# 15_FLASH-NAND_FLASH.net
KiCad netlist of a schematic drawn in Altium Designer
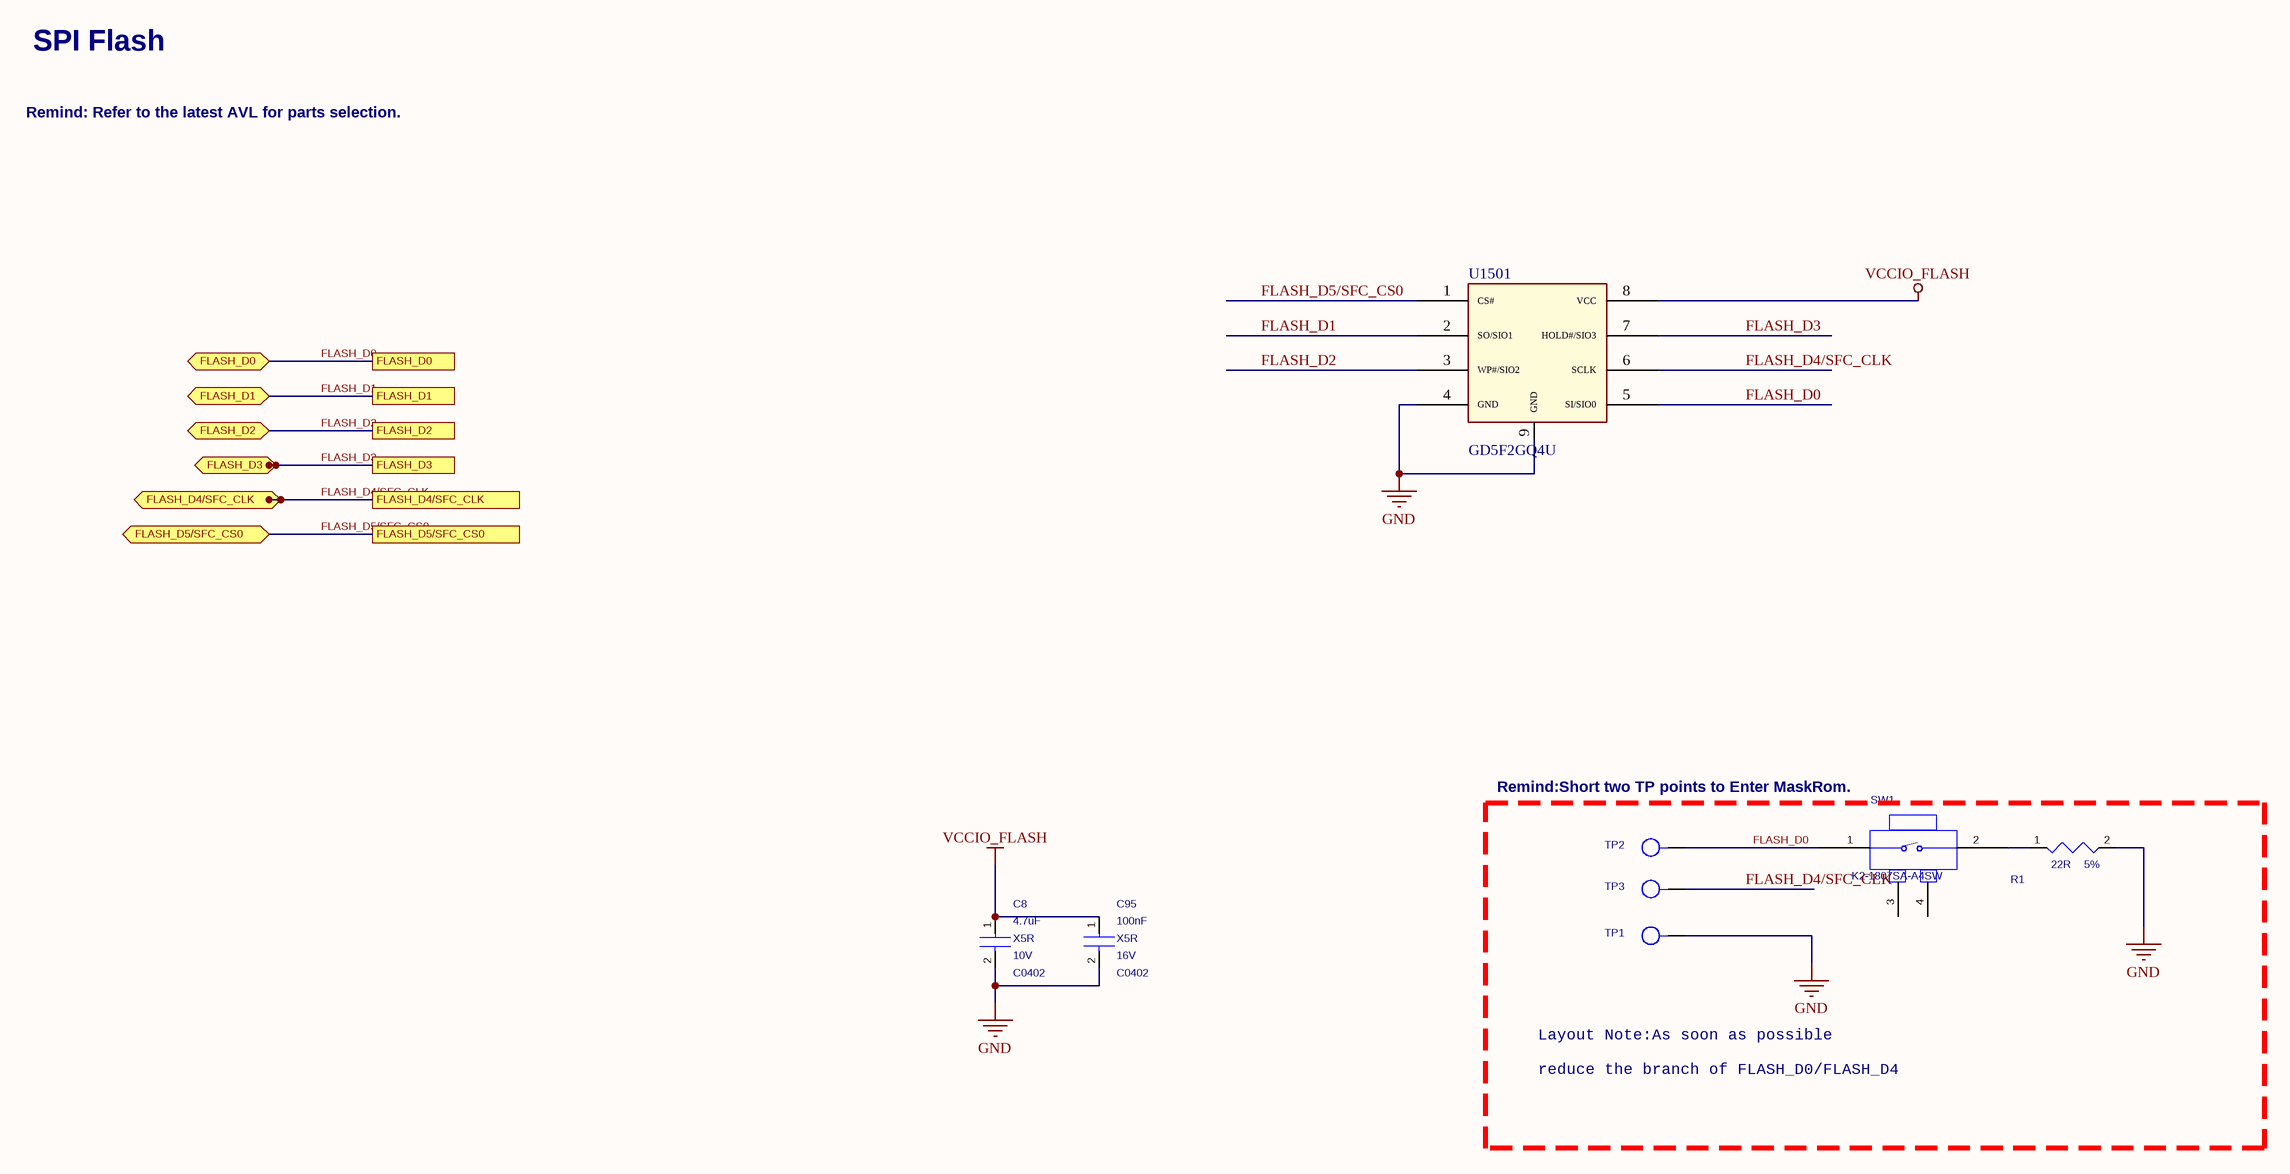
[diagram p0: 15_FLASH-NAND_FLASH.SchDoc]

(export (version "E")
  (design (tool "Eeschema 10.0.6"))
  (components
    (comp (ref "C8")
      (value "4.7uF")
      (footprint "C0402")
      (description "cap,4.70uF,+/-10%,10V,X5R,C0402")
      (fields
        (field (name "DIELECTRIC") "X5R")
        (field (name "VOLTAGE") "10V")
        (field (name "TOLERANCE") "10%")
        (field (name "MANUFACTURER") "TDK")
        (field (name "PCB DECAL") "C0402")
        (field (name "CREATED_BY") "JJJ")
      )
      (libsource (lib "*") (part "CAP_NP_2"))
    )
    (comp (ref "C95")
      (value "100nF")
      (footprint "C0402")
      (description "cap,100.00nF,+/-10%,16V,X5R,C0402")
      (fields
        (field (name "MANUFACTURER") "TDK")
        (field (name "TOLERANCE") "10%")
        (field (name "VOLTAGE") "16V")
        (field (name "DIELECTRIC") "X5R")
        (field (name "PCB DECAL") "C0402")
        (field (name "CREATED_BY") "JJJ")
      )
      (libsource (lib "*") (part "CAP_NP_2"))
    )
    (comp (ref "R1")
      (value "22R")
      (footprint "R0402")
      (description "?用厚膜电阻,22R,+/-5%,R0402,1/16W.")
      (fields
        (field (name "TOLERANCE") "5%")
        (field (name "MANUFACTURER") "YAGEO")
        (field (name "Comment") "RESISTOR")
        (field (name "CREATED_BY") "YTL")
      )
      (libsource (lib "*") (part "RESISTOR"))
    )
    (comp (ref "SW1")
      (value "K2-1807SA-A4SW")
      (footprint "P2")
      (fields (field (name "MANUFACTURER") "HRO"))
      (libsource (lib "*") (part "K2-1807SA-A4SW"))
    )
    (comp (ref "TP1") (value "TP") (footprint "TEST") (libsource (lib "*") (part "TP")))
    (comp (ref "TP2") (value "TP") (footprint "TEST") (libsource (lib "*") (part "TP")))
    (comp (ref "TP3") (value "TP") (footprint "TEST") (libsource (lib "*") (part "TP")))
    (comp (ref "U1501") (value "GD5F2GQ4U") (footprint "LGA8") (libsource (lib "amenuo") (part "GD5F2Q4U")))
  )
  (nets
    (net (code "1") (name "/FLASH_D0") (class "Default")
      (node (ref "SW1") (pin "1") (pinfunction "1_1") (pintype "passive"))
      (node (ref "TP2") (pin "1") (pinfunction "1_1") (pintype "passive"))
      (node (ref "U1501") (pin "5") (pinfunction "SI/SIO0_5") (pintype "passive"))
    )
    (net (code "2") (name "/FLASH_D1") (class "Default")
      (node (ref "U1501") (pin "2") (pinfunction "SO/SIO1_2") (pintype "passive"))
    )
    (net (code "3") (name "/FLASH_D2") (class "Default")
      (node (ref "U1501") (pin "3") (pinfunction "WP#/SIO2_3") (pintype "passive"))
    )
    (net (code "4") (name "/FLASH_D3") (class "Default")
      (node (ref "U1501") (pin "7") (pinfunction "HOLD#/SIO3_7") (pintype "passive"))
    )
    (net (code "5") (name "/FLASH_D4{slash}SFC_CLK") (class "Default")
      (node (ref "TP3") (pin "1") (pinfunction "1_1") (pintype "passive"))
      (node (ref "U1501") (pin "6") (pinfunction "SCLK_6") (pintype "passive"))
    )
    (net (code "6") (name "/FLASH_D5{slash}SFC_CS0") (class "Default")
      (node (ref "U1501") (pin "1") (pinfunction "CS#_1") (pintype "passive"))
    )
    (net (code "7") (name "GND") (class "Default")
      (node (ref "C8") (pin "2") (pinfunction "2_2") (pintype "passive"))
      (node (ref "C95") (pin "2") (pinfunction "2_2") (pintype "passive"))
      (node (ref "R1") (pin "2") (pinfunction "2_2") (pintype "passive"))
      (node (ref "TP1") (pin "1") (pinfunction "1_1") (pintype "passive"))
      (node (ref "U1501") (pin "4") (pinfunction "GND_4") (pintype "passive"))
      (node (ref "U1501") (pin "9") (pinfunction "GND_9") (pintype "passive"))
    )
    (net (code "8") (name "Net-(R1-Pad1)") (class "Default")
      (node (ref "R1") (pin "1") (pinfunction "1_1") (pintype "passive"))
      (node (ref "SW1") (pin "2") (pinfunction "2_2") (pintype "passive"))
    )
    (net (code "9") (name "VCCIO_FLASH") (class "Default")
      (node (ref "C8") (pin "1") (pinfunction "1_1") (pintype "passive"))
      (node (ref "C95") (pin "1") (pinfunction "1_1") (pintype "passive"))
      (node (ref "U1501") (pin "8") (pinfunction "VCC_8") (pintype "passive"))
    )
    (net (code "10") (name "unconnected-(SW1-Pad3)") (class "Default")
      (node (ref "SW1") (pin "3") (pinfunction "3_3") (pintype "passive"))
    )
    (net (code "11") (name "unconnected-(SW1-Pad4)") (class "Default")
      (node (ref "SW1") (pin "4") (pinfunction "4_4") (pintype "passive"))
    )
  )
)
